# bus_filter.net
KiCad netlist of a schematic drawn in Altium Designer
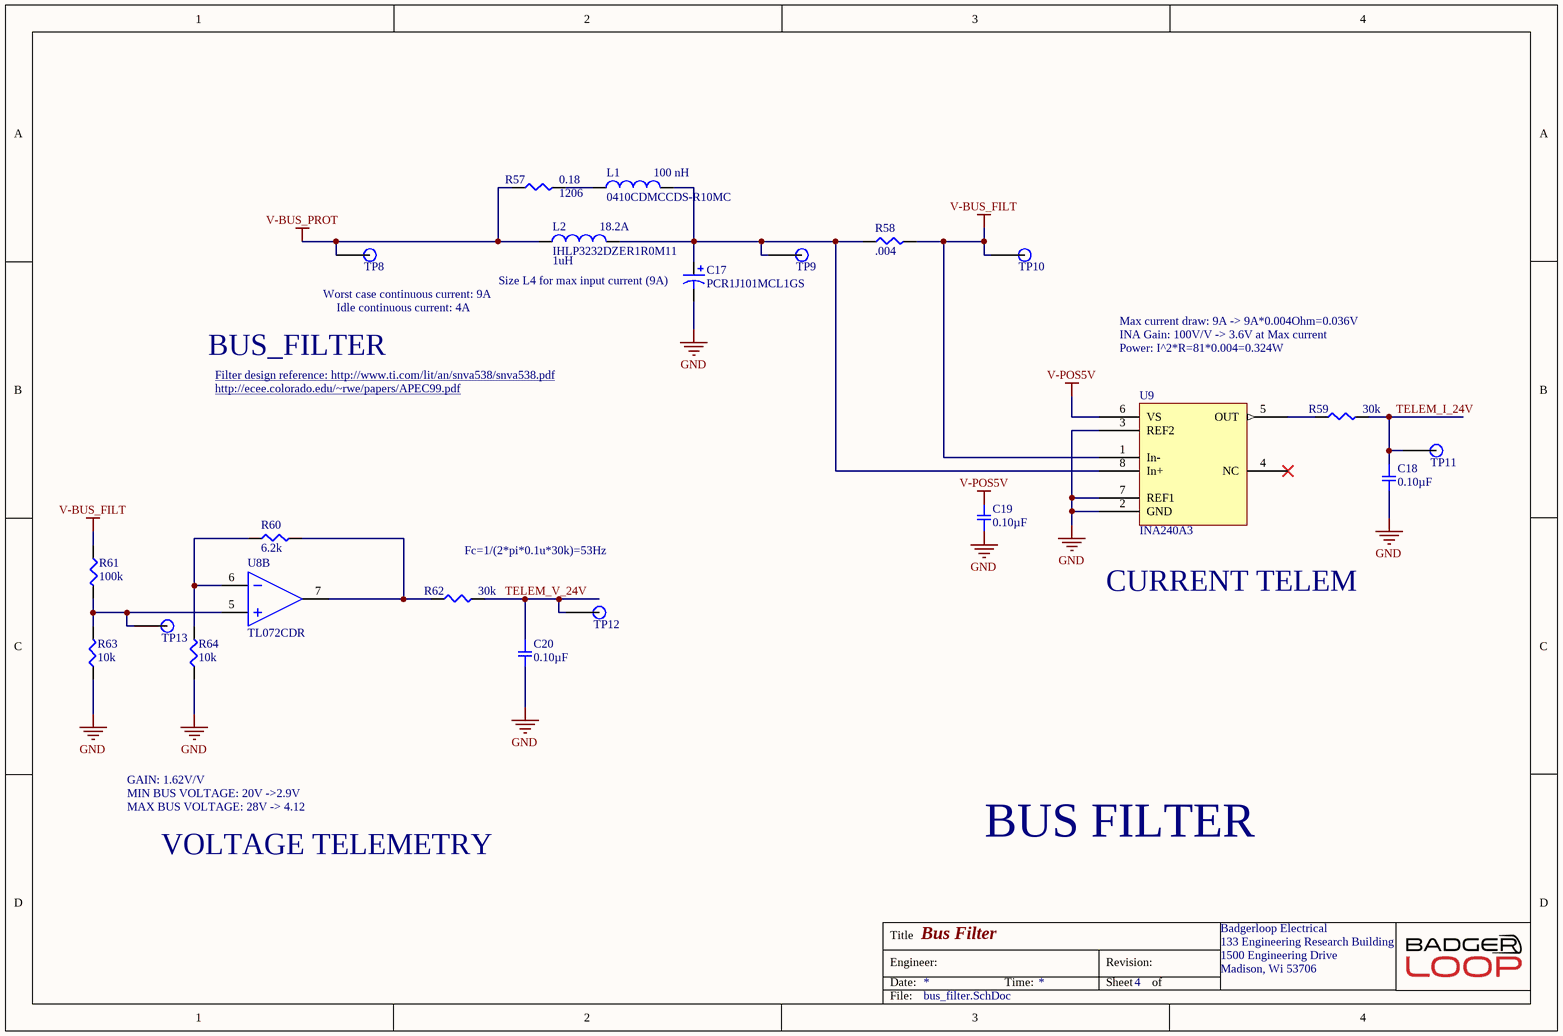
[diagram p0: bus_filter.SchDoc]

(export (version "E")
  (design (tool "Eeschema 10.0.6"))
  (components
    (comp (ref "C17")
      (value "PCR1J101MCL1GS")
      (footprint "CAPAE110103X126M")
      (description "CAP ALUM POLY 100UF 20% 63V SMD")
      (fields (field (name "MANUFACTURER") "Nichicon") (field (name "TOLERANCE") "20%"))
      (libsource (lib "capacitors") (part "PCR1J101MCL1GS"))
    )
    (comp (ref "C18")
      (value "0.10µF")
      (footprint "SMD-0805C")
      (description "CAP CER 0.1UF 16V X7R 0805")
      (fields
        (field (name "DIGI-KEY PART NUMBER") "490-1683-1-ND")
        (field (name "PART NUMBER") "GRM219R71C104KA01D")
      )
      (libsource (lib "capacitors") (part "GRM219R71C104KA01D"))
    )
    (comp (ref "C19")
      (value "0.10µF")
      (footprint "SMD-0805C")
      (description "CAP CER 0.1UF 10V U2J 0805")
      (fields
        (field (name "DIGI-KEY PART NUMBER") "490-11592-1-ND")
        (field (name "PART NUMBER") "GRM21B7U1A104JA01L")
      )
      (libsource (lib "capacitors") (part "GRM21B7U1A104JA01L"))
    )
    (comp (ref "C20")
      (value "0.10µF")
      (footprint "SMD-0805C")
      (description "CAP CER 0.1UF 16V X7R 0805")
      (fields
        (field (name "DIGI-KEY PART NUMBER") "490-1683-1-ND")
        (field (name "PART NUMBER") "GRM219R71C104KA01D")
      )
      (libsource (lib "capacitors") (part "GRM219R71C104KA01D"))
    )
    (comp (ref "L1")
      (value "0410CDMCCDS-R10MC")
      (footprint "INDM4442X20N")
      (description "Ind Chip Power Metal Compound 0.1uH 20% 2-Pin SMD T/R")
      (fields (field (name "MANUFACTURER") "Sumida") (field (name "INDUCTANCE") "100 nH"))
      (libsource (lib "inductor") (part "0410CDMCCDS-R10MC"))
    )
    (comp (ref "L2")
      (value "IHLP3232DZER1R0M11")
      (footprint "INDM8682X40N")
      (description "Fixed Inductors 1uH 20% Low Profile")
      (fields
        (field (name "MANUFACTURER") "Vishay Dale")
        (field (name "TOLERANCE") "20%")
        (field (name "CURRENT RATING") "18.2A")
        (field (name "INDUCTANCE") "1uH")
      )
      (libsource (lib "inductor") (part "IHLP3232DZER1R0M11"))
    )
    (comp (ref "R57")
      (value "0.18")
      (footprint "SMD-1206-RES")
      (description "RES SMD 0.18 OHM 1% 1/2W 1206")
      (fields
        (field (name "PART NUMBER") "ERJ-8BSFR18V")
        (field (name "DIGI-KEY PART NUMBER") "P17683CT-ND")
        (field (name "SUPPLIER DEVICE PACKAGE") "1206")
      )
      (libsource (lib "resistors") (part "ERJ-8BSFR18V"))
    )
    (comp (ref "R58")
      (value ".004")
      (footprint "SMD-1206-RES")
      (description "RES SMD 0.004 OHM 1% 1W 1206")
      (fields (field (name "MANUFACTURER") "Rohm") (field (name "MANUFACTURER PART NUMBER") "PMR18EZPFV4L00"))
      (libsource (lib "resistors") (part "PMR18EZPFV4L00"))
    )
    (comp (ref "R59")
      (value "30k")
      (footprint "SMD-0805-RES")
      (description "RES SMD 30K OHM 1% 1/8W 0805")
      (fields
        (field (name "PART NUMBER") "ERJ-6ENF3002V")
        (field (name "DIGI-KEY PART NUMBER") "P30.0KCCT-ND")
      )
      (libsource (lib "resistors") (part "ERJ-6ENF3002V"))
    )
    (comp (ref "R60")
      (value "6.2k")
      (footprint "SMD-0805-RES")
      (description "RES SMD 6.2K OHM 5% 1/2W 0805")
      (fields
        (field (name "PART NUMBER") "ERJ-P06J622V")
        (field (name "DIGI-KEY PART NUMBER") "P6.2KADCT-ND")
      )
      (libsource (lib "resistors") (part "ERJ-P06J622V"))
    )
    (comp (ref "R61")
      (value "100k")
      (footprint "SMD-0805-RES")
      (description "RES SMD 100K OHM 5% 1/2W 0805")
      (fields
        (field (name "PART NUMBER") "ERJ-P06J104V")
        (field (name "DIGI-KEY PART NUMBER") "P100KADCT-ND")
      )
      (libsource (lib "resistors") (part "ERJ-P06J104V"))
    )
    (comp (ref "R62")
      (value "30k")
      (footprint "SMD-0805-RES")
      (description "RES SMD 30K OHM 1% 1/8W 0805")
      (fields
        (field (name "PART NUMBER") "ERJ-6ENF3002V")
        (field (name "DIGI-KEY PART NUMBER") "P30.0KCCT-ND")
      )
      (libsource (lib "resistors") (part "ERJ-6ENF3002V"))
    )
    (comp (ref "R63")
      (value "10k")
      (footprint "SMD-0805-RES")
      (description "RES SMD 10K OHM 5% 1/2W 0805")
      (fields (field (name "PART NUMBER") "ERJ-P06J103V") (field (name "DIGI-KEY PART NUMBER") "P10KADCT-ND"))
      (libsource (lib "resistors") (part "ERJ-P06J103V"))
    )
    (comp (ref "R64")
      (value "10k")
      (footprint "SMD-0805-RES")
      (description "RES SMD 10K OHM 5% 1/2W 0805")
      (fields (field (name "PART NUMBER") "ERJ-P06J103V") (field (name "DIGI-KEY PART NUMBER") "P10KADCT-ND"))
      (libsource (lib "resistors") (part "ERJ-P06J103V"))
    )
    (comp (ref "TP8")
      (value "TP")
      (footprint "Test Point")
      (description "SMD TEST POINT")
      (libsource (lib "misc") (part "TP"))
    )
    (comp (ref "TP9")
      (value "TP")
      (footprint "Test Point")
      (description "SMD TEST POINT")
      (libsource (lib "misc") (part "TP"))
    )
    (comp (ref "TP10")
      (value "TP")
      (footprint "Test Point")
      (description "SMD TEST POINT")
      (libsource (lib "misc") (part "TP"))
    )
    (comp (ref "TP11")
      (value "TP")
      (footprint "Test Point")
      (description "SMD TEST POINT")
      (libsource (lib "misc") (part "TP"))
    )
    (comp (ref "TP12")
      (value "TP")
      (footprint "Test Point")
      (description "SMD TEST POINT")
      (libsource (lib "misc") (part "TP"))
    )
    (comp (ref "TP13")
      (value "TP")
      (footprint "Test Point")
      (description "SMD TEST POINT")
      (libsource (lib "misc") (part "TP"))
    )
    (comp (ref "U8")
      (value "TL072CDR")
      (footprint "SOP127P600X175-8N")
      (description "IC OPAMP JFET 3MHZ 8SOIC")
      (fields (field (name "MANUFACTURER") "Texas Instruments"))
      (libsource (lib "ic") (part "TL072CDR"))
    )
    (comp (ref "U9")
      (value "INA240A3")
      (footprint "SOIC127P600X175-8N")
      (description "IC AMP CURRENT SENSE 8-TSSOP 100V/V")
      (fields (field (name "MANUFACTURER") "Texas Instruments"))
      (libsource (lib "ic") (part "INA240A3"))
    )
  )
  (nets
    (net (code "1") (name "/TELEM_I_24V") (class "Default")
      (node (ref "C18") (pin "1") (pinfunction "1_1") (pintype "passive"))
      (node (ref "R59") (pin "2") (pinfunction "2_2") (pintype "passive"))
      (node (ref "TP11") (pin "1") (pinfunction "1_1") (pintype "passive"))
    )
    (net (code "2") (name "/TELEM_V_24V") (class "Default")
      (node (ref "C20") (pin "1") (pinfunction "1_1") (pintype "passive"))
      (node (ref "R62") (pin "2") (pinfunction "2_2") (pintype "passive"))
      (node (ref "TP12") (pin "1") (pinfunction "1_1") (pintype "passive"))
    )
    (net (code "3") (name "GND") (class "Default")
      (node (ref "C17") (pin "2") (pinfunction "2_2") (pintype "passive"))
      (node (ref "C18") (pin "2") (pinfunction "2_2") (pintype "passive"))
      (node (ref "C19") (pin "1") (pinfunction "1_1") (pintype "passive"))
      (node (ref "C20") (pin "2") (pinfunction "2_2") (pintype "passive"))
      (node (ref "R63") (pin "1") (pinfunction "1_1") (pintype "passive"))
      (node (ref "R64") (pin "1") (pinfunction "1_1") (pintype "passive"))
      (node (ref "U9") (pin "2") (pinfunction "GND_2") (pintype "power_in"))
      (node (ref "U9") (pin "3") (pinfunction "REF2_3") (pintype "passive"))
      (node (ref "U9") (pin "7") (pinfunction "REF1_7") (pintype "passive"))
    )
    (net (code "4") (name "Net-(L1-Pad1)") (class "Default")
      (node (ref "L1") (pin "1") (pinfunction "1_1") (pintype "passive"))
      (node (ref "R57") (pin "2") (pinfunction "2_2") (pintype "passive"))
    )
    (net (code "5") (name "Net-(U8B-IN+)") (class "Default")
      (node (ref "R61") (pin "2") (pinfunction "2_2") (pintype "passive"))
      (node (ref "R63") (pin "2") (pinfunction "2_2") (pintype "passive"))
      (node (ref "TP13") (pin "1") (pinfunction "1_1") (pintype "passive"))
      (node (ref "U8") (pin "5") (pinfunction "IN+_5") (pintype "passive"))
    )
    (net (code "6") (name "Net-(U8B-IN-)") (class "Default")
      (node (ref "R60") (pin "1") (pinfunction "1_1") (pintype "passive"))
      (node (ref "R64") (pin "2") (pinfunction "2_2") (pintype "passive"))
      (node (ref "U8") (pin "6") (pinfunction "IN-_6") (pintype "passive"))
    )
    (net (code "7") (name "Net-(U8B-OUT)") (class "Default")
      (node (ref "R60") (pin "2") (pinfunction "2_2") (pintype "passive"))
      (node (ref "R62") (pin "1") (pinfunction "1_1") (pintype "passive"))
      (node (ref "U8") (pin "7") (pinfunction "OUT_7") (pintype "passive"))
    )
    (net (code "8") (name "Net-(U9-In+)") (class "Default")
      (node (ref "C17") (pin "1") (pinfunction "1_1") (pintype "passive"))
      (node (ref "L1") (pin "2") (pinfunction "2_2") (pintype "passive"))
      (node (ref "L2") (pin "2") (pinfunction "2_2") (pintype "passive"))
      (node (ref "R58") (pin "1") (pinfunction "1_1") (pintype "passive"))
      (node (ref "TP9") (pin "1") (pinfunction "1_1") (pintype "passive"))
      (node (ref "U9") (pin "8") (pinfunction "In+_8") (pintype "passive"))
    )
    (net (code "9") (name "Net-(U9-OUT)") (class "Default")
      (node (ref "R59") (pin "1") (pinfunction "1_1") (pintype "passive"))
      (node (ref "U9") (pin "5") (pinfunction "OUT_5") (pintype "output"))
    )
    (net (code "10") (name "V-BUS_FILT") (class "Default")
      (node (ref "R58") (pin "2") (pinfunction "2_2") (pintype "passive"))
      (node (ref "R61") (pin "1") (pinfunction "1_1") (pintype "passive"))
      (node (ref "TP10") (pin "1") (pinfunction "1_1") (pintype "passive"))
      (node (ref "U9") (pin "1") (pinfunction "In-_1") (pintype "passive"))
    )
    (net (code "11") (name "V-BUS_PROT") (class "Default")
      (node (ref "L2") (pin "1") (pinfunction "1_1") (pintype "passive"))
      (node (ref "R57") (pin "1") (pinfunction "1_1") (pintype "passive"))
      (node (ref "TP8") (pin "1") (pinfunction "1_1") (pintype "passive"))
    )
    (net (code "12") (name "V-POS5V") (class "Default")
      (node (ref "C19") (pin "2") (pinfunction "2_2") (pintype "passive"))
      (node (ref "U9") (pin "6") (pinfunction "VS_6") (pintype "power_in"))
    )
    (net (code "13") (name "unconnected-(U9-NC-Pad4)") (class "Default")
      (node (ref "U9") (pin "4") (pinfunction "NC_4") (pintype "passive+no_connect"))
    )
  )
)
